# PP6_LCD.net
KiCad netlist of a schematic drawn in Altium Designer
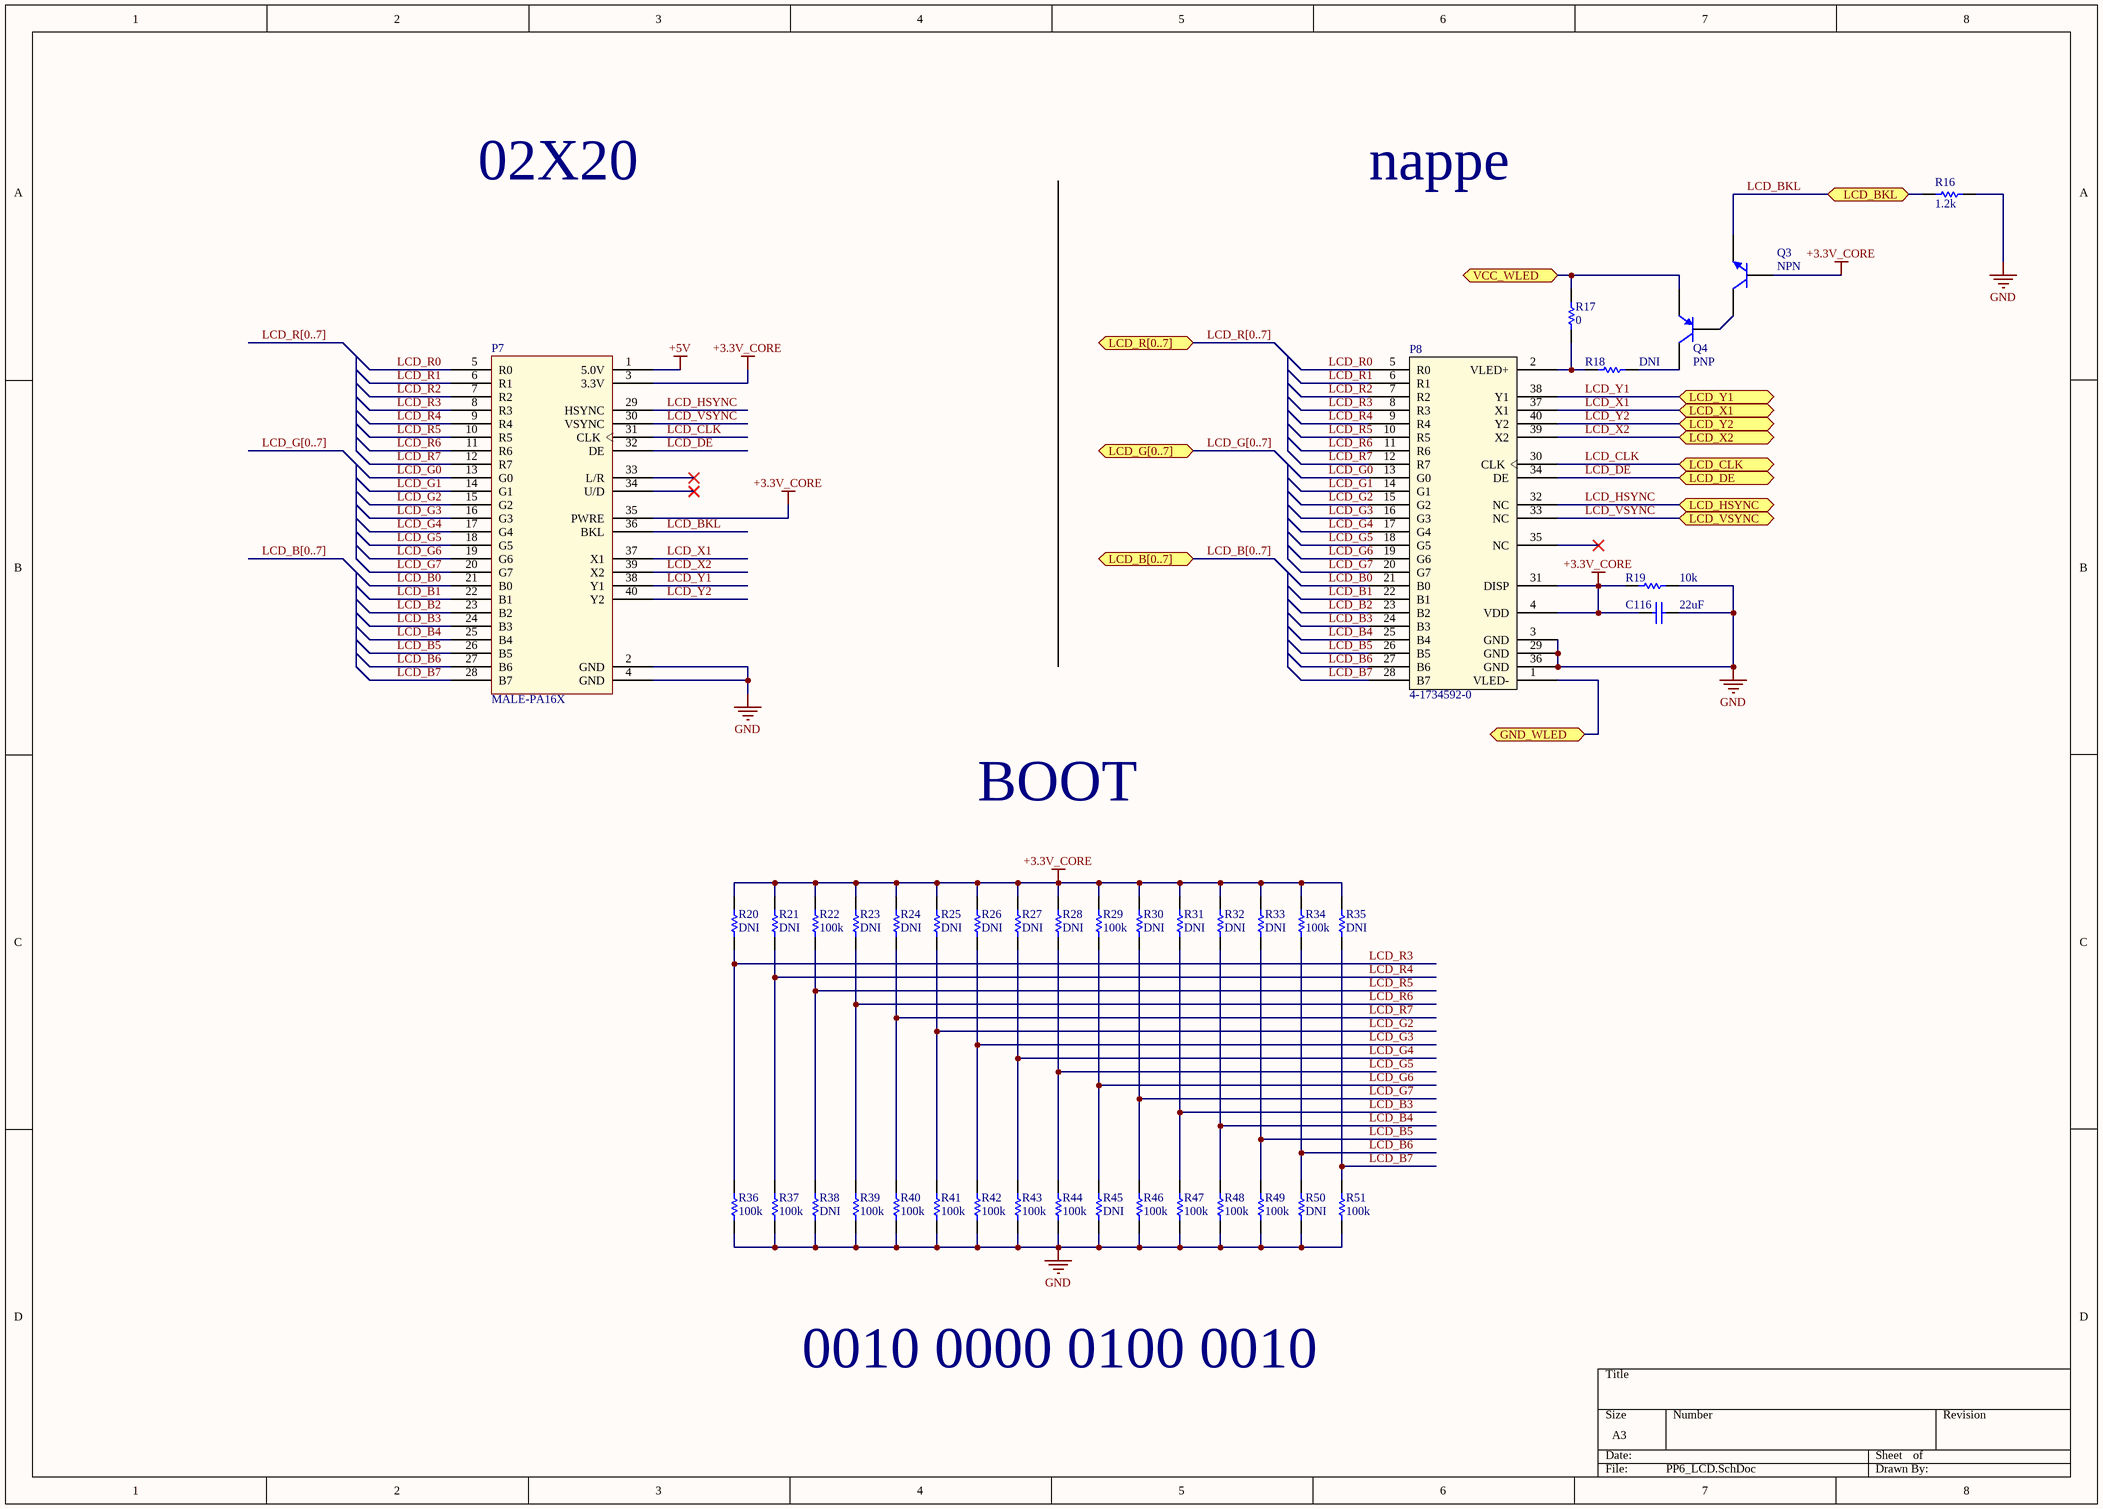
[diagram p0: PP6_LCD.SchDoc]

(export (version "E")
  (design (tool "Eeschema 10.0.6"))
  (components
    (comp (ref "C116")
      (value "22uF")
      (footprint "CAPC1608X08")
      (description "Capacitor")
      (fields (field (name "Comment") "Cap 22uF"))
      (libsource (lib "Michel") (part "Cap"))
    )
    (comp (ref "P7")
      (value "MALE-PA16X")
      (footprint "MALE-PAV16X-2x05")
      (description "Connecteur LCD et Touch screen (limande)")
      (libsource (lib "Michel") (part "MALE-PA16X"))
    )
    (comp (ref "P8")
      (value "4-1734592-0")
      (footprint "TE_4-1734592-0")
      (description "Connecteur LCD et Touch screen")
      (libsource (lib "Michel") (part "4-1734592-0"))
    )
    (comp (ref "Q3")
      (value "NPN")
      (footprint "SOT95P234X111-3N")
      (description "NPN Bipolar Transistor")
      (libsource (lib "Michel") (part "NPN"))
    )
    (comp (ref "Q4")
      (value "PNP")
      (footprint "SOT95P234X111-3N")
      (description "PNP Bipolar Transistor")
      (libsource (lib "Michel") (part "PNP"))
    )
    (comp (ref "R16")
      (value "1.2k")
      (footprint "RESC1608X05")
      (description "Resistor")
      (fields (field (name "Comment") "Res 1.2k"))
      (libsource (lib "Michel") (part "Res1"))
    )
    (comp (ref "R17")
      (value "0")
      (footprint "RESC1608X05")
      (description "Resistor")
      (fields (field (name "Comment") "Res 0 Ohm"))
      (libsource (lib "Michel") (part "Res1"))
    )
    (comp (ref "R18")
      (value "DNI")
      (footprint "RESC1608X05")
      (description "Resistor")
      (fields (field (name "Comment") "Res"))
      (libsource (lib "Michel") (part "Res1"))
    )
    (comp (ref "R19")
      (value "10k")
      (footprint "RESC1608X05")
      (description "Resistor")
      (fields (field (name "Comment") "Res 10k"))
      (libsource (lib "Michel") (part "Res1"))
    )
    (comp (ref "R20")
      (value "DNI")
      (footprint "RESC1608X05")
      (description "Resistor")
      (fields (field (name "Comment") "Res"))
      (libsource (lib "Michel") (part "Res1"))
    )
    (comp (ref "R21")
      (value "DNI")
      (footprint "RESC1608X05")
      (description "Resistor")
      (fields (field (name "Comment") "Res"))
      (libsource (lib "Michel") (part "Res1"))
    )
    (comp (ref "R22")
      (value "100k")
      (footprint "RESC1608X05")
      (description "Resistor")
      (fields (field (name "Comment") "Res 100k"))
      (libsource (lib "Michel") (part "Res1"))
    )
    (comp (ref "R23")
      (value "DNI")
      (footprint "RESC1608X05")
      (description "Resistor")
      (fields (field (name "Comment") "Res"))
      (libsource (lib "Michel") (part "Res1"))
    )
    (comp (ref "R24")
      (value "DNI")
      (footprint "RESC1608X05")
      (description "Resistor")
      (fields (field (name "Comment") "Res"))
      (libsource (lib "Michel") (part "Res1"))
    )
    (comp (ref "R25")
      (value "DNI")
      (footprint "RESC1608X05")
      (description "Resistor")
      (fields (field (name "Comment") "Res"))
      (libsource (lib "Michel") (part "Res1"))
    )
    (comp (ref "R26")
      (value "DNI")
      (footprint "RESC1608X05")
      (description "Resistor")
      (fields (field (name "Comment") "Res"))
      (libsource (lib "Michel") (part "Res1"))
    )
    (comp (ref "R27")
      (value "DNI")
      (footprint "RESC1608X05")
      (description "Resistor")
      (fields (field (name "Comment") "Res"))
      (libsource (lib "Michel") (part "Res1"))
    )
    (comp (ref "R28")
      (value "DNI")
      (footprint "RESC1608X05")
      (description "Resistor")
      (fields (field (name "Comment") "Res"))
      (libsource (lib "Michel") (part "Res1"))
    )
    (comp (ref "R29")
      (value "100k")
      (footprint "RESC1608X05")
      (description "Resistor")
      (fields (field (name "Comment") "Res 100k"))
      (libsource (lib "Michel") (part "Res1"))
    )
    (comp (ref "R30")
      (value "DNI")
      (footprint "RESC1608X05")
      (description "Resistor")
      (fields (field (name "Comment") "Res"))
      (libsource (lib "Michel") (part "Res1"))
    )
    (comp (ref "R31")
      (value "DNI")
      (footprint "RESC1608X05")
      (description "Resistor")
      (fields (field (name "Comment") "Res"))
      (libsource (lib "Michel") (part "Res1"))
    )
    (comp (ref "R32")
      (value "DNI")
      (footprint "RESC1608X05")
      (description "Resistor")
      (fields (field (name "Comment") "Res"))
      (libsource (lib "Michel") (part "Res1"))
    )
    (comp (ref "R33")
      (value "DNI")
      (footprint "RESC1608X05")
      (description "Resistor")
      (fields (field (name "Comment") "Res"))
      (libsource (lib "Michel") (part "Res1"))
    )
    (comp (ref "R34")
      (value "100k")
      (footprint "RESC1608X05")
      (description "Resistor")
      (fields (field (name "Comment") "Res 100k"))
      (libsource (lib "Michel") (part "Res1"))
    )
    (comp (ref "R35")
      (value "DNI")
      (footprint "RESC1608X05")
      (description "Resistor")
      (fields (field (name "Comment") "Res"))
      (libsource (lib "Michel") (part "Res1"))
    )
    (comp (ref "R36")
      (value "100k")
      (footprint "RESC1608X05")
      (description "Resistor")
      (fields (field (name "Comment") "Res 100k"))
      (libsource (lib "Michel") (part "Res1"))
    )
    (comp (ref "R37")
      (value "100k")
      (footprint "RESC1608X05")
      (description "Resistor")
      (fields (field (name "Comment") "Res 100k"))
      (libsource (lib "Michel") (part "Res1"))
    )
    (comp (ref "R38")
      (value "DNI")
      (footprint "RESC1608X05")
      (description "Resistor")
      (fields (field (name "Comment") "Res"))
      (libsource (lib "Michel") (part "Res1"))
    )
    (comp (ref "R39")
      (value "100k")
      (footprint "RESC1608X05")
      (description "Resistor")
      (fields (field (name "Comment") "Res 100k"))
      (libsource (lib "Michel") (part "Res1"))
    )
    (comp (ref "R40")
      (value "100k")
      (footprint "RESC1608X05")
      (description "Resistor")
      (fields (field (name "Comment") "Res 100k"))
      (libsource (lib "Michel") (part "Res1"))
    )
    (comp (ref "R41")
      (value "100k")
      (footprint "RESC1608X05")
      (description "Resistor")
      (fields (field (name "Comment") "Res 100k"))
      (libsource (lib "Michel") (part "Res1"))
    )
    (comp (ref "R42")
      (value "100k")
      (footprint "RESC1608X05")
      (description "Resistor")
      (fields (field (name "Comment") "Res 100k"))
      (libsource (lib "Michel") (part "Res1"))
    )
    (comp (ref "R43")
      (value "100k")
      (footprint "RESC1608X05")
      (description "Resistor")
      (fields (field (name "Comment") "Res 100k"))
      (libsource (lib "Michel") (part "Res1"))
    )
    (comp (ref "R44")
      (value "100k")
      (footprint "RESC1608X05")
      (description "Resistor")
      (fields (field (name "Comment") "Res 100k"))
      (libsource (lib "Michel") (part "Res1"))
    )
    (comp (ref "R45")
      (value "DNI")
      (footprint "RESC1608X05")
      (description "Resistor")
      (fields (field (name "Comment") "Res"))
      (libsource (lib "Michel") (part "Res1"))
    )
    (comp (ref "R46")
      (value "100k")
      (footprint "RESC1608X05")
      (description "Resistor")
      (fields (field (name "Comment") "Res 100k"))
      (libsource (lib "Michel") (part "Res1"))
    )
    (comp (ref "R47")
      (value "100k")
      (footprint "RESC1608X05")
      (description "Resistor")
      (fields (field (name "Comment") "Res 100k"))
      (libsource (lib "Michel") (part "Res1"))
    )
    (comp (ref "R48")
      (value "100k")
      (footprint "RESC1608X05")
      (description "Resistor")
      (fields (field (name "Comment") "Res 100k"))
      (libsource (lib "Michel") (part "Res1"))
    )
    (comp (ref "R49")
      (value "100k")
      (footprint "RESC1608X05")
      (description "Resistor")
      (fields (field (name "Comment") "Res 100k"))
      (libsource (lib "Michel") (part "Res1"))
    )
    (comp (ref "R50")
      (value "DNI")
      (footprint "RESC1608X05")
      (description "Resistor")
      (fields (field (name "Comment") "Res"))
      (libsource (lib "Michel") (part "Res1"))
    )
    (comp (ref "R51")
      (value "100k")
      (footprint "RESC1608X05")
      (description "Resistor")
      (fields (field (name "Comment") "Res 100k"))
      (libsource (lib "Michel") (part "Res1"))
    )
  )
  (nets
    (net (code "1") (name "+3.3V_CORE") (class "Default")
      (node (ref "C116") (pin "2") (pinfunction "2_2") (pintype "passive"))
      (node (ref "P7") (pin "3") (pinfunction "3.3V_3") (pintype "passive"))
      (node (ref "P7") (pin "35") (pinfunction "PWRE_35") (pintype "passive"))
      (node (ref "P8") (pin "31") (pinfunction "DISP_31") (pintype "passive"))
      (node (ref "P8") (pin "4") (pinfunction "VDD_4") (pintype "passive"))
      (node (ref "Q3") (pin "2") (pinfunction "B_2") (pintype "passive"))
      (node (ref "R19") (pin "2") (pinfunction "2_2") (pintype "passive"))
      (node (ref "R20") (pin "2") (pinfunction "2_2") (pintype "passive"))
      (node (ref "R21") (pin "2") (pinfunction "2_2") (pintype "passive"))
      (node (ref "R22") (pin "2") (pinfunction "2_2") (pintype "passive"))
      (node (ref "R23") (pin "2") (pinfunction "2_2") (pintype "passive"))
      (node (ref "R24") (pin "2") (pinfunction "2_2") (pintype "passive"))
      (node (ref "R25") (pin "2") (pinfunction "2_2") (pintype "passive"))
      (node (ref "R26") (pin "2") (pinfunction "2_2") (pintype "passive"))
      (node (ref "R27") (pin "2") (pinfunction "2_2") (pintype "passive"))
      (node (ref "R28") (pin "2") (pinfunction "2_2") (pintype "passive"))
      (node (ref "R29") (pin "2") (pinfunction "2_2") (pintype "passive"))
      (node (ref "R30") (pin "2") (pinfunction "2_2") (pintype "passive"))
      (node (ref "R31") (pin "2") (pinfunction "2_2") (pintype "passive"))
      (node (ref "R32") (pin "2") (pinfunction "2_2") (pintype "passive"))
      (node (ref "R33") (pin "2") (pinfunction "2_2") (pintype "passive"))
      (node (ref "R34") (pin "2") (pinfunction "2_2") (pintype "passive"))
      (node (ref "R35") (pin "2") (pinfunction "2_2") (pintype "passive"))
    )
    (net (code "2") (name "+5V") (class "Default")
      (node (ref "P7") (pin "1") (pinfunction "5.0V_1") (pintype "passive"))
    )
    (net (code "3") (name "/GND_WLED") (class "Default")
      (node (ref "P8") (pin "1") (pinfunction "VLED-_1") (pintype "passive"))
    )
    (net (code "4") (name "/LCD_B0") (class "Default")
      (node (ref "P7") (pin "21") (pinfunction "B0_21") (pintype "passive"))
      (node (ref "P8") (pin "21") (pinfunction "B0_21") (pintype "passive"))
    )
    (net (code "5") (name "/LCD_B1") (class "Default")
      (node (ref "P7") (pin "22") (pinfunction "B1_22") (pintype "passive"))
      (node (ref "P8") (pin "22") (pinfunction "B1_22") (pintype "passive"))
    )
    (net (code "6") (name "/LCD_B2") (class "Default")
      (node (ref "P7") (pin "23") (pinfunction "B2_23") (pintype "passive"))
      (node (ref "P8") (pin "23") (pinfunction "B2_23") (pintype "passive"))
    )
    (net (code "7") (name "/LCD_B3") (class "Default")
      (node (ref "P7") (pin "24") (pinfunction "B3_24") (pintype "passive"))
      (node (ref "P8") (pin "24") (pinfunction "B3_24") (pintype "passive"))
      (node (ref "R31") (pin "1") (pinfunction "1_1") (pintype "passive"))
      (node (ref "R47") (pin "2") (pinfunction "2_2") (pintype "passive"))
    )
    (net (code "8") (name "/LCD_B4") (class "Default")
      (node (ref "P7") (pin "25") (pinfunction "B4_25") (pintype "passive"))
      (node (ref "P8") (pin "25") (pinfunction "B4_25") (pintype "passive"))
      (node (ref "R32") (pin "1") (pinfunction "1_1") (pintype "passive"))
      (node (ref "R48") (pin "2") (pinfunction "2_2") (pintype "passive"))
    )
    (net (code "9") (name "/LCD_B5") (class "Default")
      (node (ref "P7") (pin "26") (pinfunction "B5_26") (pintype "passive"))
      (node (ref "P8") (pin "26") (pinfunction "B5_26") (pintype "passive"))
      (node (ref "R33") (pin "1") (pinfunction "1_1") (pintype "passive"))
      (node (ref "R49") (pin "2") (pinfunction "2_2") (pintype "passive"))
    )
    (net (code "10") (name "/LCD_B6") (class "Default")
      (node (ref "P7") (pin "27") (pinfunction "B6_27") (pintype "passive"))
      (node (ref "P8") (pin "27") (pinfunction "B6_27") (pintype "passive"))
      (node (ref "R34") (pin "1") (pinfunction "1_1") (pintype "passive"))
      (node (ref "R50") (pin "2") (pinfunction "2_2") (pintype "passive"))
    )
    (net (code "11") (name "/LCD_B7") (class "Default")
      (node (ref "P7") (pin "28") (pinfunction "B7_28") (pintype "passive"))
      (node (ref "P8") (pin "28") (pinfunction "B7_28") (pintype "passive"))
      (node (ref "R35") (pin "1") (pinfunction "1_1") (pintype "passive"))
      (node (ref "R51") (pin "2") (pinfunction "2_2") (pintype "passive"))
    )
    (net (code "12") (name "/LCD_BKL") (class "Default")
      (node (ref "P7") (pin "36") (pinfunction "BKL_36") (pintype "passive"))
      (node (ref "Q3") (pin "3") (pinfunction "E_3") (pintype "passive"))
      (node (ref "R16") (pin "2") (pinfunction "2_2") (pintype "passive"))
    )
    (net (code "14") (name "/LCD_CLK") (class "Default")
      (node (ref "P7") (pin "31") (pinfunction "CLK_31") (pintype "passive"))
      (node (ref "P8") (pin "30") (pinfunction "CLK_30") (pintype "passive"))
    )
    (net (code "15") (name "/LCD_DE") (class "Default")
      (node (ref "P7") (pin "32") (pinfunction "DE_32") (pintype "passive"))
      (node (ref "P8") (pin "34") (pinfunction "DE_34") (pintype "passive"))
    )
    (net (code "16") (name "/LCD_G0") (class "Default")
      (node (ref "P7") (pin "13") (pinfunction "G0_13") (pintype "passive"))
      (node (ref "P8") (pin "13") (pinfunction "G0_13") (pintype "passive"))
    )
    (net (code "17") (name "/LCD_G1") (class "Default")
      (node (ref "P7") (pin "14") (pinfunction "G1_14") (pintype "passive"))
      (node (ref "P8") (pin "14") (pinfunction "G1_14") (pintype "passive"))
    )
    (net (code "18") (name "/LCD_G2") (class "Default")
      (node (ref "P7") (pin "15") (pinfunction "G2_15") (pintype "passive"))
      (node (ref "P8") (pin "15") (pinfunction "G2_15") (pintype "passive"))
      (node (ref "R25") (pin "1") (pinfunction "1_1") (pintype "passive"))
      (node (ref "R41") (pin "2") (pinfunction "2_2") (pintype "passive"))
    )
    (net (code "19") (name "/LCD_G3") (class "Default")
      (node (ref "P7") (pin "16") (pinfunction "G3_16") (pintype "passive"))
      (node (ref "P8") (pin "16") (pinfunction "G3_16") (pintype "passive"))
      (node (ref "R26") (pin "1") (pinfunction "1_1") (pintype "passive"))
      (node (ref "R42") (pin "2") (pinfunction "2_2") (pintype "passive"))
    )
    (net (code "20") (name "/LCD_G4") (class "Default")
      (node (ref "P7") (pin "17") (pinfunction "G4_17") (pintype "passive"))
      (node (ref "P8") (pin "17") (pinfunction "G4_17") (pintype "passive"))
      (node (ref "R27") (pin "1") (pinfunction "1_1") (pintype "passive"))
      (node (ref "R43") (pin "2") (pinfunction "2_2") (pintype "passive"))
    )
    (net (code "21") (name "/LCD_G5") (class "Default")
      (node (ref "P7") (pin "18") (pinfunction "G5_18") (pintype "passive"))
      (node (ref "P8") (pin "18") (pinfunction "G5_18") (pintype "passive"))
      (node (ref "R28") (pin "1") (pinfunction "1_1") (pintype "passive"))
      (node (ref "R44") (pin "2") (pinfunction "2_2") (pintype "passive"))
    )
    (net (code "22") (name "/LCD_G6") (class "Default")
      (node (ref "P7") (pin "19") (pinfunction "G6_19") (pintype "passive"))
      (node (ref "P8") (pin "19") (pinfunction "G6_19") (pintype "passive"))
      (node (ref "R29") (pin "1") (pinfunction "1_1") (pintype "passive"))
      (node (ref "R45") (pin "2") (pinfunction "2_2") (pintype "passive"))
    )
    (net (code "23") (name "/LCD_G7") (class "Default")
      (node (ref "P7") (pin "20") (pinfunction "G7_20") (pintype "passive"))
      (node (ref "P8") (pin "20") (pinfunction "G7_20") (pintype "passive"))
      (node (ref "R30") (pin "1") (pinfunction "1_1") (pintype "passive"))
      (node (ref "R46") (pin "2") (pinfunction "2_2") (pintype "passive"))
    )
    (net (code "25") (name "/LCD_HSYNC") (class "Default")
      (node (ref "P7") (pin "29") (pinfunction "HSYNC_29") (pintype "passive"))
      (node (ref "P8") (pin "32") (pinfunction "NC_32") (pintype "passive"))
    )
    (net (code "26") (name "/LCD_R0") (class "Default")
      (node (ref "P7") (pin "5") (pinfunction "R0_5") (pintype "passive"))
      (node (ref "P8") (pin "5") (pinfunction "R0_5") (pintype "passive"))
    )
    (net (code "27") (name "/LCD_R1") (class "Default")
      (node (ref "P7") (pin "6") (pinfunction "R1_6") (pintype "passive"))
      (node (ref "P8") (pin "6") (pinfunction "R1_6") (pintype "passive"))
    )
    (net (code "28") (name "/LCD_R2") (class "Default")
      (node (ref "P7") (pin "7") (pinfunction "R2_7") (pintype "passive"))
      (node (ref "P8") (pin "7") (pinfunction "R2_7") (pintype "passive"))
    )
    (net (code "29") (name "/LCD_R3") (class "Default")
      (node (ref "P7") (pin "8") (pinfunction "R3_8") (pintype "passive"))
      (node (ref "P8") (pin "8") (pinfunction "R3_8") (pintype "passive"))
      (node (ref "R20") (pin "1") (pinfunction "1_1") (pintype "passive"))
      (node (ref "R36") (pin "2") (pinfunction "2_2") (pintype "passive"))
    )
    (net (code "30") (name "/LCD_R4") (class "Default")
      (node (ref "P7") (pin "9") (pinfunction "R4_9") (pintype "passive"))
      (node (ref "P8") (pin "9") (pinfunction "R4_9") (pintype "passive"))
      (node (ref "R21") (pin "1") (pinfunction "1_1") (pintype "passive"))
      (node (ref "R37") (pin "2") (pinfunction "2_2") (pintype "passive"))
    )
    (net (code "31") (name "/LCD_R5") (class "Default")
      (node (ref "P7") (pin "10") (pinfunction "R5_10") (pintype "passive"))
      (node (ref "P8") (pin "10") (pinfunction "R5_10") (pintype "passive"))
      (node (ref "R22") (pin "1") (pinfunction "1_1") (pintype "passive"))
      (node (ref "R38") (pin "2") (pinfunction "2_2") (pintype "passive"))
    )
    (net (code "32") (name "/LCD_R6") (class "Default")
      (node (ref "P7") (pin "11") (pinfunction "R6_11") (pintype "passive"))
      (node (ref "P8") (pin "11") (pinfunction "R6_11") (pintype "passive"))
      (node (ref "R23") (pin "1") (pinfunction "1_1") (pintype "passive"))
      (node (ref "R39") (pin "2") (pinfunction "2_2") (pintype "passive"))
    )
    (net (code "33") (name "/LCD_R7") (class "Default")
      (node (ref "P7") (pin "12") (pinfunction "R7_12") (pintype "passive"))
      (node (ref "P8") (pin "12") (pinfunction "R7_12") (pintype "passive"))
      (node (ref "R24") (pin "1") (pinfunction "1_1") (pintype "passive"))
      (node (ref "R40") (pin "2") (pinfunction "2_2") (pintype "passive"))
    )
    (net (code "35") (name "/LCD_VSYNC") (class "Default")
      (node (ref "P7") (pin "30") (pinfunction "VSYNC_30") (pintype "passive"))
      (node (ref "P8") (pin "33") (pinfunction "NC_33") (pintype "passive"))
    )
    (net (code "36") (name "/LCD_X1") (class "Default")
      (node (ref "P7") (pin "37") (pinfunction "X1_37") (pintype "passive"))
      (node (ref "P8") (pin "37") (pinfunction "X1_37") (pintype "passive"))
    )
    (net (code "37") (name "/LCD_X2") (class "Default")
      (node (ref "P7") (pin "39") (pinfunction "X2_39") (pintype "passive"))
      (node (ref "P8") (pin "39") (pinfunction "X2_39") (pintype "passive"))
    )
    (net (code "38") (name "/LCD_Y1") (class "Default")
      (node (ref "P7") (pin "38") (pinfunction "Y1_38") (pintype "passive"))
      (node (ref "P8") (pin "38") (pinfunction "Y1_38") (pintype "passive"))
    )
    (net (code "39") (name "/LCD_Y2") (class "Default")
      (node (ref "P7") (pin "40") (pinfunction "Y2_40") (pintype "passive"))
      (node (ref "P8") (pin "40") (pinfunction "Y2_40") (pintype "passive"))
    )
    (net (code "40") (name "/VCC_WLED") (class "Default")
      (node (ref "Q4") (pin "3") (pinfunction "E_3") (pintype "passive"))
      (node (ref "R17") (pin "2") (pinfunction "2_2") (pintype "passive"))
    )
    (net (code "41") (name "GND") (class "Default")
      (node (ref "C116") (pin "1") (pinfunction "1_1") (pintype "passive"))
      (node (ref "P7") (pin "2") (pinfunction "GND_2") (pintype "passive"))
      (node (ref "P7") (pin "4") (pinfunction "GND_4") (pintype "passive"))
      (node (ref "P8") (pin "29") (pinfunction "GND_29") (pintype "passive"))
      (node (ref "P8") (pin "3") (pinfunction "GND_3") (pintype "passive"))
      (node (ref "P8") (pin "36") (pinfunction "GND_36") (pintype "passive"))
      (node (ref "R16") (pin "1") (pinfunction "1_1") (pintype "passive"))
      (node (ref "R19") (pin "1") (pinfunction "1_1") (pintype "passive"))
      (node (ref "R36") (pin "1") (pinfunction "1_1") (pintype "passive"))
      (node (ref "R37") (pin "1") (pinfunction "1_1") (pintype "passive"))
      (node (ref "R38") (pin "1") (pinfunction "1_1") (pintype "passive"))
      (node (ref "R39") (pin "1") (pinfunction "1_1") (pintype "passive"))
      (node (ref "R40") (pin "1") (pinfunction "1_1") (pintype "passive"))
      (node (ref "R41") (pin "1") (pinfunction "1_1") (pintype "passive"))
      (node (ref "R42") (pin "1") (pinfunction "1_1") (pintype "passive"))
      (node (ref "R43") (pin "1") (pinfunction "1_1") (pintype "passive"))
      (node (ref "R44") (pin "1") (pinfunction "1_1") (pintype "passive"))
      (node (ref "R45") (pin "1") (pinfunction "1_1") (pintype "passive"))
      (node (ref "R46") (pin "1") (pinfunction "1_1") (pintype "passive"))
      (node (ref "R47") (pin "1") (pinfunction "1_1") (pintype "passive"))
      (node (ref "R48") (pin "1") (pinfunction "1_1") (pintype "passive"))
      (node (ref "R49") (pin "1") (pinfunction "1_1") (pintype "passive"))
      (node (ref "R50") (pin "1") (pinfunction "1_1") (pintype "passive"))
      (node (ref "R51") (pin "1") (pinfunction "1_1") (pintype "passive"))
    )
    (net (code "42") (name "Net-(P8-VLED+)") (class "Default")
      (node (ref "P8") (pin "2") (pinfunction "VLED+_2") (pintype "passive"))
      (node (ref "R17") (pin "1") (pinfunction "1_1") (pintype "passive"))
      (node (ref "R18") (pin "2") (pinfunction "2_2") (pintype "passive"))
    )
    (net (code "43") (name "Net-(Q3-C)") (class "Default")
      (node (ref "Q3") (pin "1") (pinfunction "C_1") (pintype "passive"))
      (node (ref "Q4") (pin "2") (pinfunction "B_2") (pintype "passive"))
    )
    (net (code "44") (name "Net-(Q4-C)") (class "Default")
      (node (ref "Q4") (pin "1") (pinfunction "C_1") (pintype "passive"))
      (node (ref "R18") (pin "1") (pinfunction "1_1") (pintype "passive"))
    )
    (net (code "45") (name "unconnected-(P7-L{slash}R-Pad33)") (class "Default")
      (node (ref "P7") (pin "33") (pinfunction "L/R_33") (pintype "passive+no_connect"))
    )
    (net (code "46") (name "unconnected-(P7-U{slash}D-Pad34)") (class "Default")
      (node (ref "P7") (pin "34") (pinfunction "U/D_34") (pintype "passive+no_connect"))
    )
    (net (code "47") (name "unconnected-(P8-NC-Pad35)") (class "Default")
      (node (ref "P8") (pin "35") (pinfunction "NC_35") (pintype "passive+no_connect"))
    )
  )
)
